# QSPI.net
KiCad netlist of a schematic drawn in Altium Designer
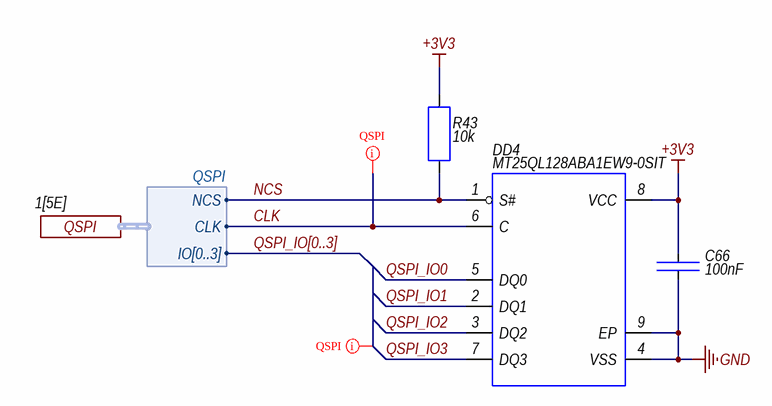
[diagram p0: QSPI.SchDoc]

(export (version "E")
  (design (tool "Eeschema 10.0.6"))
  (components
    (comp (ref "C66")
      (value "Конденсатор керам. ЧИП X5R, 10%, 0402, 0.1 мкФ")
      (footprint "Capacitor 0402")
      (description "Cap Ceramic 0.1uF 50V X5R 10% Pad SMD 0402 85C T/R")
      (fields
        (field (name "CAPACITANCE") "100nF")
        (field (name "VOLTAGE") "50V")
        (field (name "MANUFACTURER") "Murata Manufacturing")
      )
      (libsource (lib "Eleps server") (part "Nonpolar Capacitor"))
    )
    (comp (ref "DD4")
      (value "Микросхема MT25QL128ABA1EW9-0SIT")
      (footprint "8-SON")
      (description "Micron Serial NOR Flash Memory")
      (fields
        (field (name "MANUFACTURER") "Micron")
        (field (name "MANUFACTURER PART NUMBER") "MT25QL128ABA1EW9-0SIT")
        (field (name "DEVICE") "MT25QL128ABA1EW9-0SIT")
      )
      (libsource (lib "Eleps server") (part "MT25QL128ABA"))
    )
    (comp (ref "R43")
      (value "~")
      (footprint "SMD_0402")
      (fields (field (name "PART NUMBER") "Resistor_0402") (field (name "DEVICE") "10k"))
      (libsource (lib "PhLib") (part "Resistor"))
    )
  )
  (nets
    (net (code "2") (name "+3V3") (class "Default")
      (node (ref "C66") (pin "1") (pinfunction "1_1") (pintype "passive"))
      (node (ref "DD4") (pin "8") (pinfunction "VCC_8") (pintype "passive"))
      (node (ref "R43") (pin "1") (pinfunction "1_1") (pintype "passive"))
    )
    (net (code "3") (name "/CLK") (class "Default")
      (node (ref "DD4") (pin "6") (pinfunction "C_6") (pintype "passive"))
    )
    (net (code "4") (name "/NCS") (class "Default")
      (node (ref "DD4") (pin "1") (pinfunction "S#_1") (pintype "passive"))
      (node (ref "R43") (pin "2") (pinfunction "2_2") (pintype "passive"))
    )
    (net (code "5") (name "/QSPI_IO0") (class "Default")
      (node (ref "DD4") (pin "5") (pinfunction "DQ0_5") (pintype "passive"))
    )
    (net (code "6") (name "/QSPI_IO1") (class "Default")
      (node (ref "DD4") (pin "2") (pinfunction "DQ1_2") (pintype "passive"))
    )
    (net (code "7") (name "/QSPI_IO2") (class "Default")
      (node (ref "DD4") (pin "3") (pinfunction "DQ2_3") (pintype "passive"))
    )
    (net (code "8") (name "/QSPI_IO3") (class "Default")
      (node (ref "DD4") (pin "7") (pinfunction "DQ3_7") (pintype "passive"))
    )
    (net (code "11") (name "GND") (class "Default")
      (node (ref "C66") (pin "2") (pinfunction "2_2") (pintype "passive"))
      (node (ref "DD4") (pin "4") (pinfunction "VSS_4") (pintype "passive"))
      (node (ref "DD4") (pin "9") (pinfunction "EP_9") (pintype "passive"))
    )
  )
)
